# Transmitter.net
KiCad netlist of a schematic drawn in EAGLE
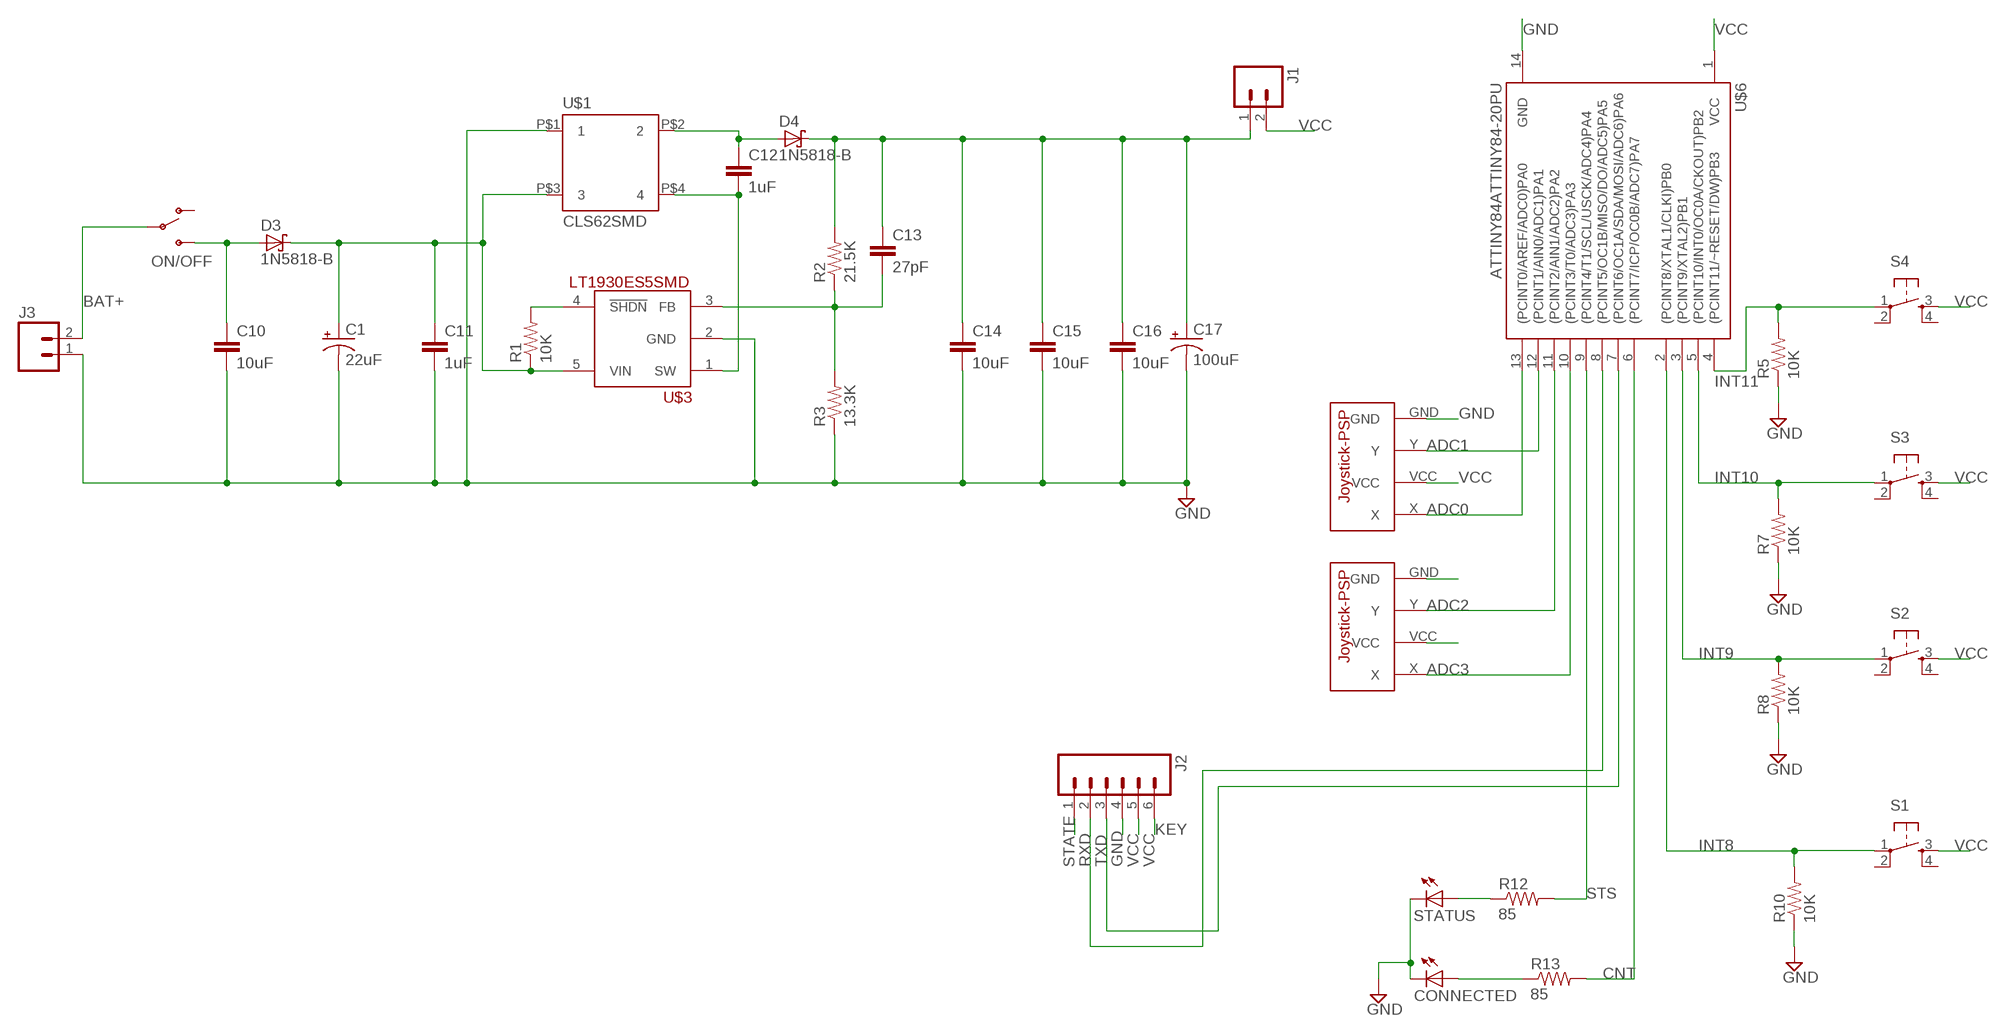
[diagram p0: schematic, sheet 1]

(export (version "E")
  (design (tool "Eeschema 10.0.6"))
  (components
    (comp (ref "C1")
      (value "22uF")
      (footprint "eagle-import:CPOL-RADIAL-10UF-25V")
      (fields (field (name "MF") "FARNELL") (field (name "MPN") "MKS2B042201F00KSSD"))
      (libsource (lib "eagle-import") (part "CAP_POLPTH2"))
    )
    (comp (ref "C10")
      (value "10uF")
      (footprint "eagle-import:CAP-PTH-SMALLEZ")
      (libsource (lib "eagle-import") (part "CAPEZ"))
    )
    (comp (ref "C11")
      (value "1uF")
      (footprint "eagle-import:CAP-PTH-SMALLEZ")
      (libsource (lib "eagle-import") (part "CAPEZ"))
    )
    (comp (ref "C12")
      (value "1uF")
      (footprint "eagle-import:CAP-PTH-SMALLEZ")
      (libsource (lib "eagle-import") (part "CAPEZ"))
    )
    (comp (ref "C13")
      (value "27pF")
      (footprint "eagle-import:CAP-PTH-SMALLEZ")
      (libsource (lib "eagle-import") (part "CAPEZ"))
    )
    (comp (ref "C14")
      (value "10uF")
      (footprint "eagle-import:CAP-PTH-SMALLEZ")
      (libsource (lib "eagle-import") (part "CAPEZ"))
    )
    (comp (ref "C15")
      (value "10uF")
      (footprint "eagle-import:CAP-PTH-SMALLEZ")
      (libsource (lib "eagle-import") (part "CAPEZ"))
    )
    (comp (ref "C16")
      (value "10uF")
      (footprint "eagle-import:CAP-PTH-SMALLEZ")
      (libsource (lib "eagle-import") (part "CAPEZ"))
    )
    (comp (ref "C17")
      (value "100uF")
      (footprint "eagle-import:CPOL-RADIAL-10UF-25V")
      (libsource (lib "eagle-import") (part "CAP_POLPTH2"))
    )
    (comp (ref "CONNECTED")
      (value "LED5MM")
      (footprint "eagle-import:LED5MM")
      (libsource (lib "eagle-import") (part "LED5MM"))
    )
    (comp (ref "D3")
      (value "1N5818-B")
      (footprint "eagle-import:DO41-7.6")
      (libsource (lib "eagle-import") (part "1N5818-B"))
    )
    (comp (ref "D4")
      (value "1N5818-B")
      (footprint "eagle-import:DO41-7.6")
      (libsource (lib "eagle-import") (part "1N5818-B"))
    )
    (comp (ref "J1")
      (value "M02PTH")
      (footprint "eagle-import:1X02")
      (libsource (lib "eagle-import") (part "M02PTH"))
    )
    (comp (ref "J2")
      (value "M06NO_SILK_FEMALE_PTH")
      (footprint "eagle-import:1X06_NO_SILK")
      (libsource (lib "eagle-import") (part "M06NO_SILK_FEMALE_PTH"))
    )
    (comp (ref "J3")
      (value "M021X02_NO_SILK")
      (footprint "eagle-import:1X02_NO_SILK")
      (libsource (lib "eagle-import") (part "M021X02_NO_SILK"))
    )
    (comp (ref "ON/OFF")
      (value "SWITCH-SPDTKIT")
      (footprint "eagle-import:SWITCH-SPDT_KIT")
      (libsource (lib "eagle-import") (part "SWITCH-SPDTKIT"))
    )
    (comp (ref "R1")
      (value "10K")
      (footprint "eagle-import:AXIAL-0.4")
      (libsource (lib "eagle-import") (part "SparkFun-Resistors_RESISTORPTH-1/4W"))
    )
    (comp (ref "R2")
      (value "21.5K")
      (footprint "eagle-import:AXIAL-0.4")
      (libsource (lib "eagle-import") (part "SparkFun-Resistors_RESISTORPTH-1/4W"))
    )
    (comp (ref "R3")
      (value "13.3K")
      (footprint "eagle-import:AXIAL-0.4")
      (libsource (lib "eagle-import") (part "SparkFun-Resistors_RESISTORPTH-1/4W"))
    )
    (comp (ref "R5")
      (value "10K")
      (footprint "eagle-import:AXIAL-0.4")
      (libsource (lib "eagle-import") (part "RESISTORPTH-1/4W"))
    )
    (comp (ref "R7")
      (value "10K")
      (footprint "eagle-import:AXIAL-0.4")
      (libsource (lib "eagle-import") (part "RESISTORPTH-1/4W"))
    )
    (comp (ref "R8")
      (value "10K")
      (footprint "eagle-import:AXIAL-0.4")
      (libsource (lib "eagle-import") (part "RESISTORPTH-1/4W"))
    )
    (comp (ref "R10")
      (value "10K")
      (footprint "eagle-import:AXIAL-0.4")
      (libsource (lib "eagle-import") (part "RESISTORPTH-1/4W"))
    )
    (comp (ref "R12")
      (value "85")
      (footprint "eagle-import:AXIAL-0.4")
      (libsource (lib "eagle-import") (part "RESISTORPTH-1/4W"))
    )
    (comp (ref "R13")
      (value "85")
      (footprint "eagle-import:AXIAL-0.4")
      (libsource (lib "eagle-import") (part "RESISTORPTH-1/4W"))
    )
    (comp (ref "S1")
      (value "TAC_SWITCHPTH")
      (footprint "eagle-import:TACTILE-PTH")
      (libsource (lib "eagle-import") (part "TAC_SWITCHPTH"))
    )
    (comp (ref "S2")
      (value "TAC_SWITCHPTH")
      (footprint "eagle-import:TACTILE-PTH")
      (libsource (lib "eagle-import") (part "TAC_SWITCHPTH"))
    )
    (comp (ref "S3")
      (value "TAC_SWITCHPTH")
      (footprint "eagle-import:TACTILE-PTH")
      (libsource (lib "eagle-import") (part "TAC_SWITCHPTH"))
    )
    (comp (ref "S4")
      (value "TAC_SWITCHPTH")
      (footprint "eagle-import:TACTILE-PTH")
      (libsource (lib "eagle-import") (part "TAC_SWITCHPTH"))
    )
    (comp (ref "STATUS")
      (value "LED5MM")
      (footprint "eagle-import:LED5MM")
      (libsource (lib "eagle-import") (part "LED5MM"))
    )
    (comp (ref "U$1")
      (value "CLS62SMD")
      (footprint "eagle-import:CLS62")
      (libsource (lib "eagle-import") (part "CLS62SMD"))
    )
    (comp (ref "U$2")
      (value "JOYSTICK-PSP1000")
      (footprint "eagle-import:JOYSTICK-PSP1000")
      (libsource (lib "eagle-import") (part "JOYSTICK-PSP1000"))
    )
    (comp (ref "U$3")
      (value "LT1930ES5SMD")
      (footprint "eagle-import:LT1930ES5")
      (libsource (lib "eagle-import") (part "LT1930ES5SMD"))
    )
    (comp (ref "U$5")
      (value "JOYSTICK-PSP1000")
      (footprint "eagle-import:JOYSTICK-PSP1000")
      (libsource (lib "eagle-import") (part "JOYSTICK-PSP1000"))
    )
    (comp (ref "U$6")
      (value "ATTINY84ATTINY84-20PU")
      (footprint "eagle-import:DIL14")
      (libsource (lib "eagle-import") (part "ATTINY84ATTINY84-20PU"))
    )
  )
  (nets
    (net (code "1") (name "/ADC0") (class "Default")
      (node (ref "U$2") (pin "X") (pinfunction "X_X") (pintype "bidirectional"))
      (node (ref "U$6") (pin "13") (pinfunction "(PCINT0/AREF/ADC0)PA0_13") (pintype "bidirectional"))
    )
    (net (code "2") (name "/ADC1") (class "Default")
      (node (ref "U$2") (pin "Y") (pinfunction "Y_Y") (pintype "bidirectional"))
      (node (ref "U$6") (pin "12") (pinfunction "(PCINT1/AIN0/ADC1)PA1_12") (pintype "bidirectional"))
    )
    (net (code "3") (name "/ADC2") (class "Default")
      (node (ref "U$5") (pin "Y") (pinfunction "Y_Y") (pintype "bidirectional"))
      (node (ref "U$6") (pin "11") (pinfunction "(PCINT2/AIN1/ADC2)PA2_11") (pintype "bidirectional"))
    )
    (net (code "4") (name "/ADC3") (class "Default")
      (node (ref "U$5") (pin "X") (pinfunction "X_X") (pintype "bidirectional"))
      (node (ref "U$6") (pin "10") (pinfunction "(PCINT3/T0/ADC3)PA3_10") (pintype "bidirectional"))
    )
    (net (code "5") (name "/BAT+") (class "Default")
      (node (ref "J3") (pin "2") (pinfunction "2_2") (pintype "passive"))
      (node (ref "ON/OFF") (pin "2") (pinfunction "P_2") (pintype "passive"))
    )
    (net (code "6") (name "/CNT") (class "Default")
      (node (ref "R13") (pin "P$2") (pinfunction "2_P$2") (pintype "passive"))
      (node (ref "U$6") (pin "6") (pinfunction "(PCINT7/ICP/OC0B/ADC7)PA7_6") (pintype "bidirectional"))
    )
    (net (code "7") (name "/INT8") (class "Default")
      (node (ref "R10") (pin "P$2") (pinfunction "2_P$2") (pintype "passive"))
      (node (ref "S1") (pin "1") (pinfunction "1_1") (pintype "passive"))
      (node (ref "U$6") (pin "2") (pinfunction "(PCINT8/XTAL1/CLKI)PB0_2") (pintype "bidirectional"))
    )
    (net (code "8") (name "/INT9") (class "Default")
      (node (ref "R8") (pin "P$2") (pinfunction "2_P$2") (pintype "passive"))
      (node (ref "S2") (pin "1") (pinfunction "1_1") (pintype "passive"))
      (node (ref "U$6") (pin "3") (pinfunction "(PCINT9/XTAL2)PB1_3") (pintype "bidirectional"))
    )
    (net (code "9") (name "/INT10") (class "Default")
      (node (ref "R7") (pin "P$2") (pinfunction "2_P$2") (pintype "passive"))
      (node (ref "S3") (pin "1") (pinfunction "1_1") (pintype "passive"))
      (node (ref "U$6") (pin "5") (pinfunction "(PCINT10/INT0/OC0A/CKOUT)PB2_5") (pintype "bidirectional"))
    )
    (net (code "10") (name "/INT11") (class "Default")
      (node (ref "R5") (pin "P$2") (pinfunction "2_P$2") (pintype "passive"))
      (node (ref "S4") (pin "1") (pinfunction "1_1") (pintype "passive"))
      (node (ref "U$6") (pin "4") (pinfunction "(PCINT11/~{RESET/DW})PB3_4") (pintype "bidirectional"))
    )
    (net (code "11") (name "/RXD") (class "Default")
      (node (ref "J2") (pin "2") (pinfunction "2_2") (pintype "passive"))
      (node (ref "U$6") (pin "8") (pinfunction "(PCINT5/OC1B/MISO/DO/ADC5)PA5_8") (pintype "bidirectional"))
    )
    (net (code "12") (name "/STATE") (class "Default")
      (node (ref "J2") (pin "1") (pinfunction "1_1") (pintype "passive"))
    )
    (net (code "13") (name "/STS") (class "Default")
      (node (ref "R12") (pin "P$2") (pinfunction "2_P$2") (pintype "passive"))
      (node (ref "U$6") (pin "9") (pinfunction "(PCINT4/T1/SCL/USCK/ADC4)PA4_9") (pintype "bidirectional"))
    )
    (net (code "14") (name "/TXD") (class "Default")
      (node (ref "J2") (pin "3") (pinfunction "3_3") (pintype "passive"))
      (node (ref "U$6") (pin "7") (pinfunction "(PCINT6/OC1A/SDA/MOSI/ADC6)PA6_7") (pintype "bidirectional"))
    )
    (net (code "15") (name "/VCC") (class "Default")
      (node (ref "J1") (pin "2") (pinfunction "2_2") (pintype "passive"))
      (node (ref "J2") (pin "5") (pinfunction "5_5") (pintype "passive"))
      (node (ref "J2") (pin "6") (pinfunction "6_6") (pintype "passive"))
      (node (ref "S1") (pin "3") (pinfunction "3_3") (pintype "passive"))
      (node (ref "S2") (pin "3") (pinfunction "3_3") (pintype "passive"))
      (node (ref "S3") (pin "3") (pinfunction "3_3") (pintype "passive"))
      (node (ref "S4") (pin "3") (pinfunction "3_3") (pintype "passive"))
      (node (ref "U$2") (pin "VCC") (pinfunction "VCC_VCC") (pintype "bidirectional"))
      (node (ref "U$5") (pin "VCC") (pinfunction "VCC_VCC") (pintype "bidirectional"))
      (node (ref "U$6") (pin "1") (pinfunction "VCC_1") (pintype "bidirectional"))
    )
    (net (code "16") (name "GND") (class "Default")
      (node (ref "C1") (pin "2") (pinfunction "-_2") (pintype "passive"))
      (node (ref "C10") (pin "2") (pinfunction "2_2") (pintype "passive"))
      (node (ref "C11") (pin "2") (pinfunction "2_2") (pintype "passive"))
      (node (ref "C14") (pin "2") (pinfunction "2_2") (pintype "passive"))
      (node (ref "C15") (pin "2") (pinfunction "2_2") (pintype "passive"))
      (node (ref "C16") (pin "2") (pinfunction "2_2") (pintype "passive"))
      (node (ref "C17") (pin "2") (pinfunction "-_2") (pintype "passive"))
      (node (ref "CONNECTED") (pin "K") (pinfunction "C_K") (pintype "passive"))
      (node (ref "J2") (pin "4") (pinfunction "4_4") (pintype "passive"))
      (node (ref "J3") (pin "1") (pinfunction "1_1") (pintype "passive"))
      (node (ref "R10") (pin "P$1") (pinfunction "1_P$1") (pintype "passive"))
      (node (ref "R3") (pin "P$1") (pinfunction "1_P$1") (pintype "passive"))
      (node (ref "R5") (pin "P$1") (pinfunction "1_P$1") (pintype "passive"))
      (node (ref "R7") (pin "P$1") (pinfunction "1_P$1") (pintype "passive"))
      (node (ref "R8") (pin "P$1") (pinfunction "1_P$1") (pintype "passive"))
      (node (ref "STATUS") (pin "K") (pinfunction "C_K") (pintype "passive"))
      (node (ref "U$1") (pin "P$1") (pinfunction "1_P$1") (pintype "bidirectional"))
      (node (ref "U$2") (pin "GND") (pinfunction "GND_GND") (pintype "bidirectional"))
      (node (ref "U$3") (pin "2") (pinfunction "GND_2") (pintype "power_in"))
      (node (ref "U$5") (pin "GND") (pinfunction "GND_GND") (pintype "bidirectional"))
      (node (ref "U$6") (pin "14") (pinfunction "GND_14") (pintype "bidirectional"))
    )
    (net (code "17") (name "Net-(C1-+)") (class "Default")
      (node (ref "C1") (pin "1") (pinfunction "+_1") (pintype "passive"))
      (node (ref "C11") (pin "1") (pinfunction "1_1") (pintype "passive"))
      (node (ref "D3") (pin "C") (pinfunction "C_C") (pintype "passive"))
      (node (ref "R1") (pin "P$1") (pinfunction "1_P$1") (pintype "passive"))
      (node (ref "U$1") (pin "P$3") (pinfunction "3_P$3") (pintype "bidirectional"))
      (node (ref "U$3") (pin "5") (pinfunction "VIN_5") (pintype "power_in"))
    )
    (net (code "18") (name "Net-(C17-+)") (class "Default")
      (node (ref "C13") (pin "1") (pinfunction "1_1") (pintype "passive"))
      (node (ref "C14") (pin "1") (pinfunction "1_1") (pintype "passive"))
      (node (ref "C15") (pin "1") (pinfunction "1_1") (pintype "passive"))
      (node (ref "C16") (pin "1") (pinfunction "1_1") (pintype "passive"))
      (node (ref "C17") (pin "1") (pinfunction "+_1") (pintype "passive"))
      (node (ref "D4") (pin "C") (pinfunction "C_C") (pintype "passive"))
      (node (ref "J1") (pin "1") (pinfunction "1_1") (pintype "passive"))
      (node (ref "R2") (pin "P$2") (pinfunction "2_P$2") (pintype "passive"))
    )
    (net (code "19") (name "Net-(ON/OFF-S)") (class "Default")
      (node (ref "C10") (pin "1") (pinfunction "1_1") (pintype "passive"))
      (node (ref "D3") (pin "A") (pinfunction "A_A") (pintype "passive"))
      (node (ref "ON/OFF") (pin "3") (pinfunction "S_3") (pintype "passive"))
    )
    (net (code "20") (name "Net-(R1-2)") (class "Default")
      (node (ref "R1") (pin "P$2") (pinfunction "2_P$2") (pintype "passive"))
      (node (ref "U$3") (pin "4") (pinfunction "~{SHDN}_4") (pintype "input"))
    )
    (net (code "21") (name "Net-(R2-1)") (class "Default")
      (node (ref "C13") (pin "2") (pinfunction "2_2") (pintype "passive"))
      (node (ref "R2") (pin "P$1") (pinfunction "1_P$1") (pintype "passive"))
      (node (ref "R3") (pin "P$2") (pinfunction "2_P$2") (pintype "passive"))
      (node (ref "U$3") (pin "3") (pinfunction "FB_3") (pintype "input"))
    )
    (net (code "22") (name "Net-(R12-1)") (class "Default")
      (node (ref "R12") (pin "P$1") (pinfunction "1_P$1") (pintype "passive"))
      (node (ref "STATUS") (pin "A") (pinfunction "A_A") (pintype "passive"))
    )
    (net (code "23") (name "Net-(R13-1)") (class "Default")
      (node (ref "CONNECTED") (pin "A") (pinfunction "A_A") (pintype "passive"))
      (node (ref "R13") (pin "P$1") (pinfunction "1_P$1") (pintype "passive"))
    )
    (net (code "24") (name "Net-(U$1-2)") (class "Default")
      (node (ref "C12") (pin "1") (pinfunction "1_1") (pintype "passive"))
      (node (ref "D4") (pin "A") (pinfunction "A_A") (pintype "passive"))
      (node (ref "U$1") (pin "P$2") (pinfunction "2_P$2") (pintype "bidirectional"))
    )
    (net (code "25") (name "Net-(U$1-4)") (class "Default")
      (node (ref "C12") (pin "2") (pinfunction "2_2") (pintype "passive"))
      (node (ref "U$1") (pin "P$4") (pinfunction "4_P$4") (pintype "bidirectional"))
      (node (ref "U$3") (pin "1") (pinfunction "SW_1") (pintype "input"))
    )
    (net (code "26") (name "unconnected-(ON/OFF-O-Pad1)") (class "Default")
      (node (ref "ON/OFF") (pin "1") (pinfunction "O_1") (pintype "passive"))
    )
    (net (code "27") (name "unconnected-(S1-Pad2)") (class "Default")
      (node (ref "S1") (pin "2") (pinfunction "2_2") (pintype "passive"))
    )
    (net (code "28") (name "unconnected-(S1-Pad4)") (class "Default")
      (node (ref "S1") (pin "4") (pinfunction "4_4") (pintype "passive"))
    )
    (net (code "29") (name "unconnected-(S2-Pad2)") (class "Default")
      (node (ref "S2") (pin "2") (pinfunction "2_2") (pintype "passive"))
    )
    (net (code "30") (name "unconnected-(S2-Pad4)") (class "Default")
      (node (ref "S2") (pin "4") (pinfunction "4_4") (pintype "passive"))
    )
    (net (code "31") (name "unconnected-(S3-Pad2)") (class "Default")
      (node (ref "S3") (pin "2") (pinfunction "2_2") (pintype "passive"))
    )
    (net (code "32") (name "unconnected-(S3-Pad4)") (class "Default")
      (node (ref "S3") (pin "4") (pinfunction "4_4") (pintype "passive"))
    )
    (net (code "33") (name "unconnected-(S4-Pad2)") (class "Default")
      (node (ref "S4") (pin "2") (pinfunction "2_2") (pintype "passive"))
    )
    (net (code "34") (name "unconnected-(S4-Pad4)") (class "Default")
      (node (ref "S4") (pin "4") (pinfunction "4_4") (pintype "passive"))
    )
  )
)
